# POWER.net
KiCad netlist of a schematic drawn in Altium Designer
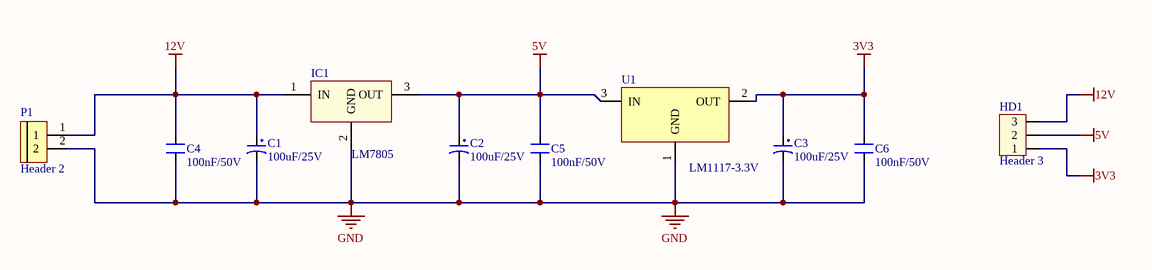
[diagram p0: POWER.SchDoc]

(export (version "E")
  (design (tool "Eeschema 10.0.6"))
  (components
    (comp (ref "C1")
      (value "100uF/25V")
      (footprint "CP1.5/3.4")
      (description "Cap 100uF/35V - 470uF/16V")
      (libsource (lib "syhaunguyen") (part "CP3"))
    )
    (comp (ref "C2")
      (value "100uF/25V")
      (footprint "CP1.5/3.4")
      (description "Cap 100uF/35V - 470uF/16V")
      (libsource (lib "syhaunguyen") (part "CP3"))
    )
    (comp (ref "C3")
      (value "100uF/25V")
      (footprint "CP1.5/3.4")
      (description "Cap 100uF/35V - 470uF/16V")
      (libsource (lib "syhaunguyen") (part "CP3"))
    )
    (comp (ref "C4")
      (value "100nF/50V")
      (footprint "CN1.5")
      (description "Cap np 682pF => 104pF")
      (libsource (lib "syhaunguyen") (part "CN1.5"))
    )
    (comp (ref "C5")
      (value "100nF/50V")
      (footprint "CN1.5")
      (description "Cap np 682pF => 104pF")
      (libsource (lib "syhaunguyen") (part "CN1.5"))
    )
    (comp (ref "C6")
      (value "100nF/50V")
      (footprint "CN1.5")
      (description "Cap np 682pF => 104pF")
      (libsource (lib "syhaunguyen") (part "CN1.5"))
    )
    (comp (ref "HD1")
      (value "Header 3")
      (footprint "HED3T")
      (description "Header 3 (Green)")
      (libsource (lib "syhaunguyen") (part "Hed3"))
    )
    (comp (ref "IC1")
      (value "LM7805")
      (footprint "QTO-220")
      (description "On ap +, from + 5 to + 24VDC")
      (libsource (lib "syhaunguyen") (part "LM78xx"))
    )
    (comp (ref "P1")
      (value "Header 2")
      (footprint "BIG_Header 2")
      (description "Big Header 2")
      (libsource (lib "Cty1") (part "Header 2"))
    )
    (comp (ref "U1")
      (value "LM1117-3.3V")
      (footprint "SOT223-4N")
      (description "800mA Low-Dropout Linear Regulator")
      (fields (field (name "CREATOR") "Nguyen Ba Bien"))
      (libsource (lib "Cty1") (part "LM1117"))
    )
  )
  (nets
    (net (code "1") (name "3V3") (class "Default")
      (node (ref "C3") (pin "1") (pinfunction "1_1") (pintype "passive"))
      (node (ref "C6") (pin "2") (pinfunction "2_2") (pintype "passive"))
      (node (ref "HD1") (pin "1") (pinfunction "1_1") (pintype "passive"))
      (node (ref "U1") (pin "2") (pinfunction "OUT_2") (pintype "passive"))
    )
    (net (code "2") (name "5V") (class "Default")
      (node (ref "C2") (pin "1") (pinfunction "1_1") (pintype "passive"))
      (node (ref "C5") (pin "2") (pinfunction "2_2") (pintype "passive"))
      (node (ref "HD1") (pin "2") (pinfunction "2_2") (pintype "passive"))
      (node (ref "IC1") (pin "3") (pinfunction "OUT_3") (pintype "passive"))
      (node (ref "U1") (pin "3") (pinfunction "IN_3") (pintype "passive"))
    )
    (net (code "3") (name "12V") (class "Default")
      (node (ref "C1") (pin "1") (pinfunction "1_1") (pintype "passive"))
      (node (ref "C4") (pin "2") (pinfunction "2_2") (pintype "passive"))
      (node (ref "HD1") (pin "3") (pinfunction "3_3") (pintype "passive"))
      (node (ref "IC1") (pin "1") (pinfunction "IN_1") (pintype "passive"))
      (node (ref "P1") (pin "1") (pinfunction "1_1") (pintype "passive"))
    )
    (net (code "4") (name "GND") (class "Default")
      (node (ref "C1") (pin "2") (pinfunction "2_2") (pintype "passive"))
      (node (ref "C2") (pin "2") (pinfunction "2_2") (pintype "passive"))
      (node (ref "C3") (pin "2") (pinfunction "2_2") (pintype "passive"))
      (node (ref "C4") (pin "1") (pinfunction "1_1") (pintype "passive"))
      (node (ref "C5") (pin "1") (pinfunction "1_1") (pintype "passive"))
      (node (ref "C6") (pin "1") (pinfunction "1_1") (pintype "passive"))
      (node (ref "IC1") (pin "2") (pinfunction "GND_2") (pintype "passive"))
      (node (ref "P1") (pin "2") (pinfunction "2_2") (pintype "passive"))
      (node (ref "U1") (pin "1") (pinfunction "GND_1") (pintype "passive"))
    )
  )
)
